# module_ESP07.net
KiCad netlist of a schematic drawn in EAGLE
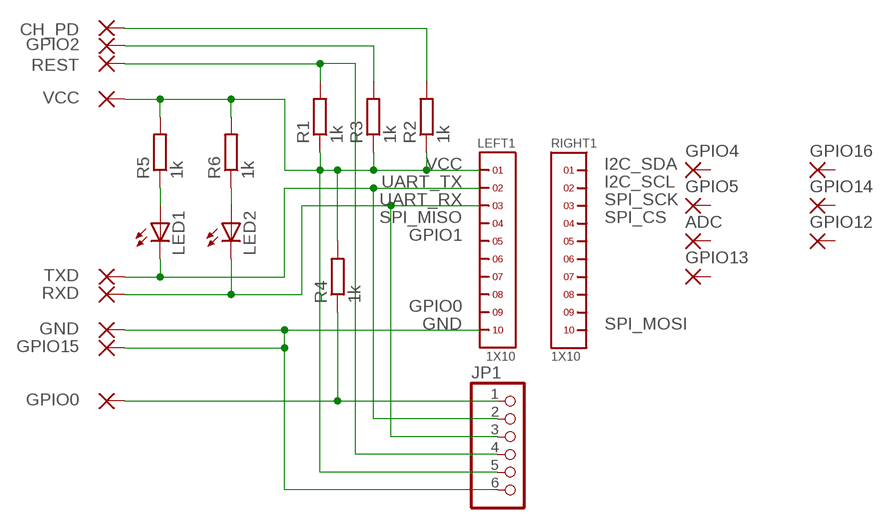
[diagram p0: schematic, sheet 1]

(export (version "E")
  (design (tool "Eeschema 10.0.6"))
  (components
    (comp (ref "ADC")
      (value "WIREPADSMD1,27-254")
      (footprint "eagle-import:SMD1,27-2,54")
      (libsource (lib "eagle-import") (part "WIREPADSMD1,27-254"))
    )
    (comp (ref "CH_PD")
      (value "WIREPADSMD1,27-254")
      (footprint "eagle-import:SMD1,27-2,54")
      (libsource (lib "eagle-import") (part "WIREPADSMD1,27-254"))
    )
    (comp (ref "GND")
      (value "WIREPADSMD1,27-254")
      (footprint "eagle-import:SMD1,27-2,54")
      (libsource (lib "eagle-import") (part "WIREPADSMD1,27-254"))
    )
    (comp (ref "GPIO0")
      (value "WIREPADSMD1,27-254")
      (footprint "eagle-import:SMD1,27-2,54")
      (libsource (lib "eagle-import") (part "WIREPADSMD1,27-254"))
    )
    (comp (ref "GPIO2")
      (value "WIREPADSMD1,27-254")
      (footprint "eagle-import:SMD1,27-2,54")
      (libsource (lib "eagle-import") (part "WIREPADSMD1,27-254"))
    )
    (comp (ref "GPIO4")
      (value "WIREPADSMD1,27-254")
      (footprint "eagle-import:SMD1,27-2,54")
      (libsource (lib "eagle-import") (part "WIREPADSMD1,27-254"))
    )
    (comp (ref "GPIO5")
      (value "WIREPADSMD1,27-254")
      (footprint "eagle-import:SMD1,27-2,54")
      (libsource (lib "eagle-import") (part "WIREPADSMD1,27-254"))
    )
    (comp (ref "GPIO12")
      (value "WIREPADSMD1,27-254")
      (footprint "eagle-import:SMD1,27-2,54")
      (libsource (lib "eagle-import") (part "WIREPADSMD1,27-254"))
    )
    (comp (ref "GPIO13")
      (value "WIREPADSMD1,27-254")
      (footprint "eagle-import:SMD1,27-2,54")
      (libsource (lib "eagle-import") (part "WIREPADSMD1,27-254"))
    )
    (comp (ref "GPIO14")
      (value "WIREPADSMD1,27-254")
      (footprint "eagle-import:SMD1,27-2,54")
      (libsource (lib "eagle-import") (part "WIREPADSMD1,27-254"))
    )
    (comp (ref "GPIO15")
      (value "WIREPADSMD1,27-254")
      (footprint "eagle-import:SMD1,27-2,54")
      (libsource (lib "eagle-import") (part "WIREPADSMD1,27-254"))
    )
    (comp (ref "GPIO16")
      (value "WIREPADSMD1,27-254")
      (footprint "eagle-import:SMD1,27-2,54")
      (libsource (lib "eagle-import") (part "WIREPADSMD1,27-254"))
    )
    (comp (ref "JP1")
      (value "PINHD-1X6")
      (footprint "eagle-import:1X06")
      (libsource (lib "eagle-import") (part "PINHD-1X6"))
    )
    (comp (ref "LED1")
      (value "LEDCHIPLED_0603")
      (footprint "eagle-import:CHIPLED_0603")
      (libsource (lib "eagle-import") (part "LEDCHIPLED_0603"))
    )
    (comp (ref "LED2")
      (value "LEDCHIPLED_0603")
      (footprint "eagle-import:CHIPLED_0603")
      (libsource (lib "eagle-import") (part "LEDCHIPLED_0603"))
    )
    (comp (ref "LEFT1")
      (value "1X10")
      (footprint "eagle-import:1X10")
      (libsource (lib "eagle-import") (part "1X10"))
    )
    (comp (ref "R1")
      (value "1k")
      (footprint "eagle-import:R0603")
      (libsource (lib "eagle-import") (part "R-EU_R0603"))
    )
    (comp (ref "R2")
      (value "1k")
      (footprint "eagle-import:R0603")
      (libsource (lib "eagle-import") (part "R-EU_R0603"))
    )
    (comp (ref "R3")
      (value "1k")
      (footprint "eagle-import:R0603")
      (libsource (lib "eagle-import") (part "R-EU_R0603"))
    )
    (comp (ref "R4")
      (value "1k")
      (footprint "eagle-import:R0603")
      (libsource (lib "eagle-import") (part "R-EU_R0603"))
    )
    (comp (ref "R5")
      (value "1k")
      (footprint "eagle-import:R0603")
      (libsource (lib "eagle-import") (part "R-EU_R0603"))
    )
    (comp (ref "R6")
      (value "1k")
      (footprint "eagle-import:R0603")
      (libsource (lib "eagle-import") (part "R-EU_R0603"))
    )
    (comp (ref "REST")
      (value "WIREPADSMD1,27-254")
      (footprint "eagle-import:SMD1,27-2,54")
      (libsource (lib "eagle-import") (part "WIREPADSMD1,27-254"))
    )
    (comp (ref "RIGHT1")
      (value "1X10")
      (footprint "eagle-import:1X10")
      (libsource (lib "eagle-import") (part "1X10"))
    )
    (comp (ref "RXD")
      (value "WIREPADSMD1,27-254")
      (footprint "eagle-import:SMD1,27-2,54")
      (libsource (lib "eagle-import") (part "WIREPADSMD1,27-254"))
    )
    (comp (ref "TXD")
      (value "WIREPADSMD1,27-254")
      (footprint "eagle-import:SMD1,27-2,54")
      (libsource (lib "eagle-import") (part "WIREPADSMD1,27-254"))
    )
    (comp (ref "VCC")
      (value "WIREPADSMD1,27-254")
      (footprint "eagle-import:SMD1,27-2,54")
      (libsource (lib "eagle-import") (part "WIREPADSMD1,27-254"))
    )
  )
  (nets
    (net (code "1") (name "Net-(CH_PD-P)") (class "Default")
      (node (ref "CH_PD") (pin "1") (pinfunction "P_1") (pintype "passive"))
      (node (ref "R2") (pin "2") (pinfunction "2_2") (pintype "passive"))
    )
    (net (code "2") (name "Net-(GND-P)") (class "Default")
      (node (ref "GND") (pin "1") (pinfunction "P_1") (pintype "passive"))
      (node (ref "GPIO15") (pin "1") (pinfunction "P_1") (pintype "passive"))
      (node (ref "JP1") (pin "6") (pinfunction "6_6") (pintype "passive"))
      (node (ref "LEFT1") (pin "10") (pinfunction "10_10") (pintype "bidirectional"))
    )
    (net (code "3") (name "Net-(GPIO0-P)") (class "Default")
      (node (ref "GPIO0") (pin "1") (pinfunction "P_1") (pintype "passive"))
      (node (ref "JP1") (pin "1") (pinfunction "1_1") (pintype "passive"))
      (node (ref "R4") (pin "1") (pinfunction "1_1") (pintype "passive"))
    )
    (net (code "4") (name "Net-(GPIO2-P)") (class "Default")
      (node (ref "GPIO2") (pin "1") (pinfunction "P_1") (pintype "passive"))
      (node (ref "R3") (pin "2") (pinfunction "2_2") (pintype "passive"))
    )
    (net (code "5") (name "Net-(LED1-PadA)") (class "Default")
      (node (ref "LED1") (pin "A") (pinfunction "A_A") (pintype "passive"))
      (node (ref "R5") (pin "1") (pinfunction "1_1") (pintype "passive"))
    )
    (net (code "6") (name "Net-(LED2-PadA)") (class "Default")
      (node (ref "LED2") (pin "A") (pinfunction "A_A") (pintype "passive"))
      (node (ref "R6") (pin "1") (pinfunction "1_1") (pintype "passive"))
    )
    (net (code "7") (name "Net-(REST-P)") (class "Default")
      (node (ref "JP1") (pin "4") (pinfunction "4_4") (pintype "passive"))
      (node (ref "R1") (pin "2") (pinfunction "2_2") (pintype "passive"))
      (node (ref "REST") (pin "1") (pinfunction "P_1") (pintype "passive"))
    )
    (net (code "8") (name "Net-(RXD-P)") (class "Default")
      (node (ref "JP1") (pin "3") (pinfunction "3_3") (pintype "passive"))
      (node (ref "LED2") (pin "C") (pinfunction "C_C") (pintype "passive"))
      (node (ref "LEFT1") (pin "3") (pinfunction "3_3") (pintype "bidirectional"))
      (node (ref "RXD") (pin "1") (pinfunction "P_1") (pintype "passive"))
    )
    (net (code "9") (name "Net-(TXD-P)") (class "Default")
      (node (ref "JP1") (pin "2") (pinfunction "2_2") (pintype "passive"))
      (node (ref "LED1") (pin "C") (pinfunction "C_C") (pintype "passive"))
      (node (ref "LEFT1") (pin "2") (pinfunction "2_2") (pintype "bidirectional"))
      (node (ref "TXD") (pin "1") (pinfunction "P_1") (pintype "passive"))
    )
    (net (code "10") (name "Net-(VCC-P)") (class "Default")
      (node (ref "JP1") (pin "5") (pinfunction "5_5") (pintype "passive"))
      (node (ref "LEFT1") (pin "1") (pinfunction "1_1") (pintype "bidirectional"))
      (node (ref "R1") (pin "1") (pinfunction "1_1") (pintype "passive"))
      (node (ref "R2") (pin "1") (pinfunction "1_1") (pintype "passive"))
      (node (ref "R3") (pin "1") (pinfunction "1_1") (pintype "passive"))
      (node (ref "R4") (pin "2") (pinfunction "2_2") (pintype "passive"))
      (node (ref "R5") (pin "2") (pinfunction "2_2") (pintype "passive"))
      (node (ref "R6") (pin "2") (pinfunction "2_2") (pintype "passive"))
      (node (ref "VCC") (pin "1") (pinfunction "P_1") (pintype "passive"))
    )
    (net (code "11") (name "unconnected-(ADC-P-Pad1)") (class "Default")
      (node (ref "ADC") (pin "1") (pinfunction "P_1") (pintype "passive"))
    )
    (net (code "12") (name "unconnected-(GPIO4-P-Pad1)") (class "Default")
      (node (ref "GPIO4") (pin "1") (pinfunction "P_1") (pintype "passive"))
    )
    (net (code "13") (name "unconnected-(GPIO5-P-Pad1)") (class "Default")
      (node (ref "GPIO5") (pin "1") (pinfunction "P_1") (pintype "passive"))
    )
    (net (code "14") (name "unconnected-(GPIO12-P-Pad1)") (class "Default")
      (node (ref "GPIO12") (pin "1") (pinfunction "P_1") (pintype "passive"))
    )
    (net (code "15") (name "unconnected-(GPIO13-P-Pad1)") (class "Default")
      (node (ref "GPIO13") (pin "1") (pinfunction "P_1") (pintype "passive"))
    )
    (net (code "16") (name "unconnected-(GPIO14-P-Pad1)") (class "Default")
      (node (ref "GPIO14") (pin "1") (pinfunction "P_1") (pintype "passive"))
    )
    (net (code "17") (name "unconnected-(GPIO16-P-Pad1)") (class "Default")
      (node (ref "GPIO16") (pin "1") (pinfunction "P_1") (pintype "passive"))
    )
    (net (code "18") (name "unconnected-(LEFT1-Pad4)") (class "Default")
      (node (ref "LEFT1") (pin "4") (pinfunction "4_4") (pintype "bidirectional"))
    )
    (net (code "19") (name "unconnected-(LEFT1-Pad5)") (class "Default")
      (node (ref "LEFT1") (pin "5") (pinfunction "5_5") (pintype "bidirectional"))
    )
    (net (code "20") (name "unconnected-(LEFT1-Pad6)") (class "Default")
      (node (ref "LEFT1") (pin "6") (pinfunction "6_6") (pintype "bidirectional"))
    )
    (net (code "21") (name "unconnected-(LEFT1-Pad7)") (class "Default")
      (node (ref "LEFT1") (pin "7") (pinfunction "7_7") (pintype "bidirectional"))
    )
    (net (code "22") (name "unconnected-(LEFT1-Pad8)") (class "Default")
      (node (ref "LEFT1") (pin "8") (pinfunction "8_8") (pintype "bidirectional"))
    )
    (net (code "23") (name "unconnected-(LEFT1-Pad9)") (class "Default")
      (node (ref "LEFT1") (pin "9") (pinfunction "9_9") (pintype "bidirectional"))
    )
    (net (code "24") (name "unconnected-(RIGHT1-Pad1)") (class "Default")
      (node (ref "RIGHT1") (pin "1") (pinfunction "1_1") (pintype "bidirectional"))
    )
    (net (code "25") (name "unconnected-(RIGHT1-Pad2)") (class "Default")
      (node (ref "RIGHT1") (pin "2") (pinfunction "2_2") (pintype "bidirectional"))
    )
    (net (code "26") (name "unconnected-(RIGHT1-Pad3)") (class "Default")
      (node (ref "RIGHT1") (pin "3") (pinfunction "3_3") (pintype "bidirectional"))
    )
    (net (code "27") (name "unconnected-(RIGHT1-Pad4)") (class "Default")
      (node (ref "RIGHT1") (pin "4") (pinfunction "4_4") (pintype "bidirectional"))
    )
    (net (code "28") (name "unconnected-(RIGHT1-Pad5)") (class "Default")
      (node (ref "RIGHT1") (pin "5") (pinfunction "5_5") (pintype "bidirectional"))
    )
    (net (code "29") (name "unconnected-(RIGHT1-Pad6)") (class "Default")
      (node (ref "RIGHT1") (pin "6") (pinfunction "6_6") (pintype "bidirectional"))
    )
    (net (code "30") (name "unconnected-(RIGHT1-Pad7)") (class "Default")
      (node (ref "RIGHT1") (pin "7") (pinfunction "7_7") (pintype "bidirectional"))
    )
    (net (code "31") (name "unconnected-(RIGHT1-Pad8)") (class "Default")
      (node (ref "RIGHT1") (pin "8") (pinfunction "8_8") (pintype "bidirectional"))
    )
    (net (code "32") (name "unconnected-(RIGHT1-Pad9)") (class "Default")
      (node (ref "RIGHT1") (pin "9") (pinfunction "9_9") (pintype "bidirectional"))
    )
    (net (code "33") (name "unconnected-(RIGHT1-Pad10)") (class "Default")
      (node (ref "RIGHT1") (pin "10") (pinfunction "10_10") (pintype "bidirectional"))
    )
  )
)
